# component-LMT70.net
KiCad netlist of a schematic drawn in EAGLE
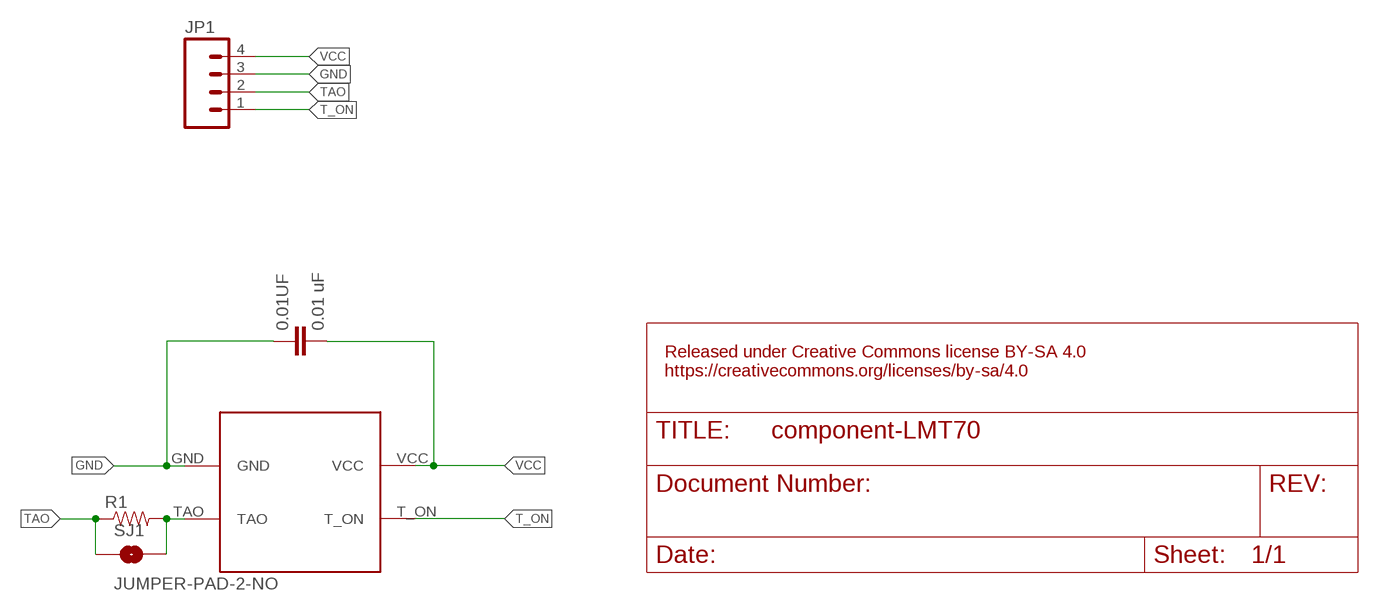
[diagram p0: schematic, sheet 1]

(export (version "E")
  (design (tool "Eeschema 10.0.6"))
  (components
    (comp (ref "0.01UF")
      (value "0.01 uF")
      (footprint "eagle-import:0603-CAP")
      (libsource (lib "eagle-import") (part "CAP0603-CAP"))
    )
    (comp (ref "JP1")
      (value "M04NO_SILK_ALL_ROUND")
      (footprint "eagle-import:1X04_NO_SILK_ALL_ROUND")
      (libsource (lib "eagle-import") (part "M04NO_SILK_ALL_ROUND"))
    )
    (comp (ref "R1")
      (value "RESISTOR0603-RES")
      (footprint "eagle-import:0603-RES")
      (libsource (lib "eagle-import") (part "RESISTOR0603-RES"))
    )
    (comp (ref "SJ1")
      (value "JUMPER-PAD-2-NO")
      (footprint "eagle-import:PAD-JUMPER-2-NO_NO_SILK")
      (libsource (lib "eagle-import") (part "JUMPER-PAD-2-NO"))
    )
    (comp (ref "U$1")
      (value "LMT70")
      (footprint "eagle-import:LMT-70")
      (libsource (lib "eagle-import") (part "LMT70"))
    )
  )
  (nets
    (net (code "1") (name "GND") (class "Default")
      (node (ref "0.01UF") (pin "1") (pinfunction "1_1") (pintype "passive"))
      (node (ref "JP1") (pin "3") (pinfunction "3_3") (pintype "passive"))
      (node (ref "U$1") (pin "GND") (pinfunction "GND_GND") (pintype "bidirectional"))
    )
    (net (code "2") (name "Net-(R1-Pad2)") (class "Default")
      (node (ref "R1") (pin "2") (pinfunction "2_2") (pintype "passive"))
      (node (ref "SJ1") (pin "2") (pinfunction "2_2") (pintype "passive"))
      (node (ref "U$1") (pin "TAO") (pinfunction "TAO_TAO") (pintype "bidirectional"))
    )
    (net (code "3") (name "TAO") (class "Default")
      (node (ref "JP1") (pin "2") (pinfunction "2_2") (pintype "passive"))
      (node (ref "R1") (pin "1") (pinfunction "1_1") (pintype "passive"))
      (node (ref "SJ1") (pin "1") (pinfunction "1_1") (pintype "passive"))
    )
    (net (code "4") (name "T_ON") (class "Default")
      (node (ref "JP1") (pin "1") (pinfunction "1_1") (pintype "passive"))
      (node (ref "U$1") (pin "T_ON") (pinfunction "T_ON_T_ON") (pintype "bidirectional"))
    )
    (net (code "5") (name "VCC") (class "Default")
      (node (ref "0.01UF") (pin "2") (pinfunction "2_2") (pintype "passive"))
      (node (ref "JP1") (pin "4") (pinfunction "4_4") (pintype "passive"))
      (node (ref "U$1") (pin "VCC") (pinfunction "VCC_VCC") (pintype "bidirectional"))
    )
  )
)
